# sensors.net
KiCad netlist of a schematic drawn in Altium Designer
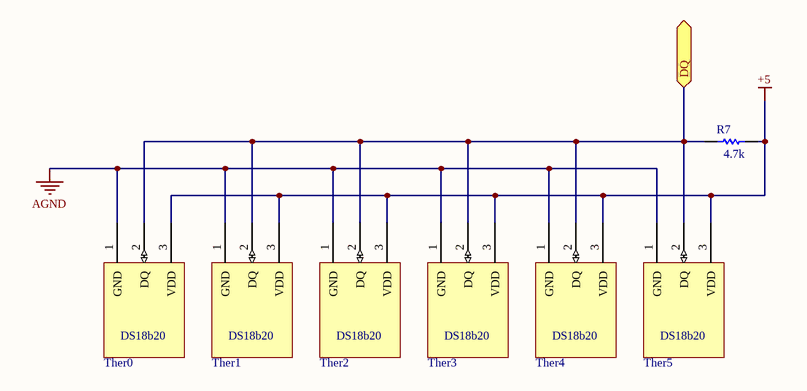
[diagram p0: sensors.SchDoc]

(export (version "E")
  (design (tool "Eeschema 10.0.6"))
  (components
    (comp (ref "R7")
      (value "4.7k")
      (footprint "0805(M)")
      (fields (field (name "Comment") "Res"))
      (libsource (lib "Self Establish") (part "Res"))
    )
    (comp (ref "Ther0")
      (value "18b20")
      (footprint "TO-92A(DIP)")
      (description "DS18B20 Programmable Resolution 1-Wire® Digital Thermometer")
      (libsource (lib "Self Establish") (part "18b20"))
    )
    (comp (ref "Ther1")
      (value "18b20")
      (footprint "TO-92A(DIP)")
      (description "DS18B20 Programmable Resolution 1-Wire® Digital Thermometer")
      (libsource (lib "Self Establish") (part "18b20"))
    )
    (comp (ref "Ther2")
      (value "18b20")
      (footprint "TO-92A(DIP)")
      (description "DS18B20 Programmable Resolution 1-Wire® Digital Thermometer")
      (libsource (lib "Self Establish") (part "18b20"))
    )
    (comp (ref "Ther3")
      (value "18b20")
      (footprint "TO-92A(DIP)")
      (description "DS18B20 Programmable Resolution 1-Wire® Digital Thermometer")
      (libsource (lib "Self Establish") (part "18b20"))
    )
    (comp (ref "Ther4")
      (value "18b20")
      (footprint "TO-92A(DIP)")
      (description "DS18B20 Programmable Resolution 1-Wire® Digital Thermometer")
      (libsource (lib "Self Establish") (part "18b20"))
    )
    (comp (ref "Ther5")
      (value "18b20")
      (footprint "TO-92A(DIP)")
      (description "DS18B20 Programmable Resolution 1-Wire® Digital Thermometer")
      (libsource (lib "Self Establish") (part "18b20"))
    )
  )
  (nets
    (net (code "1") (name "+5") (class "Default")
      (node (ref "R7") (pin "2") (pinfunction "2_2") (pintype "passive"))
      (node (ref "Ther0") (pin "3") (pinfunction "VDD_3") (pintype "power_in"))
      (node (ref "Ther1") (pin "3") (pinfunction "VDD_3") (pintype "power_in"))
      (node (ref "Ther2") (pin "3") (pinfunction "VDD_3") (pintype "power_in"))
      (node (ref "Ther3") (pin "3") (pinfunction "VDD_3") (pintype "power_in"))
      (node (ref "Ther4") (pin "3") (pinfunction "VDD_3") (pintype "power_in"))
      (node (ref "Ther5") (pin "3") (pinfunction "VDD_3") (pintype "power_in"))
    )
    (net (code "2") (name "/DQ") (class "Default")
      (node (ref "R7") (pin "1") (pinfunction "1_1") (pintype "passive"))
      (node (ref "Ther0") (pin "2") (pinfunction "DQ_2") (pintype "bidirectional"))
      (node (ref "Ther1") (pin "2") (pinfunction "DQ_2") (pintype "bidirectional"))
      (node (ref "Ther2") (pin "2") (pinfunction "DQ_2") (pintype "bidirectional"))
      (node (ref "Ther3") (pin "2") (pinfunction "DQ_2") (pintype "bidirectional"))
      (node (ref "Ther4") (pin "2") (pinfunction "DQ_2") (pintype "bidirectional"))
      (node (ref "Ther5") (pin "2") (pinfunction "DQ_2") (pintype "bidirectional"))
    )
    (net (code "3") (name "AGND") (class "Default")
      (node (ref "Ther0") (pin "1") (pinfunction "GND_1") (pintype "power_in"))
      (node (ref "Ther1") (pin "1") (pinfunction "GND_1") (pintype "power_in"))
      (node (ref "Ther2") (pin "1") (pinfunction "GND_1") (pintype "power_in"))
      (node (ref "Ther3") (pin "1") (pinfunction "GND_1") (pintype "power_in"))
      (node (ref "Ther4") (pin "1") (pinfunction "GND_1") (pintype "power_in"))
      (node (ref "Ther5") (pin "1") (pinfunction "GND_1") (pintype "power_in"))
    )
  )
)
